# EBN_OLED_V01.net
KiCad netlist of a schematic drawn in EAGLE
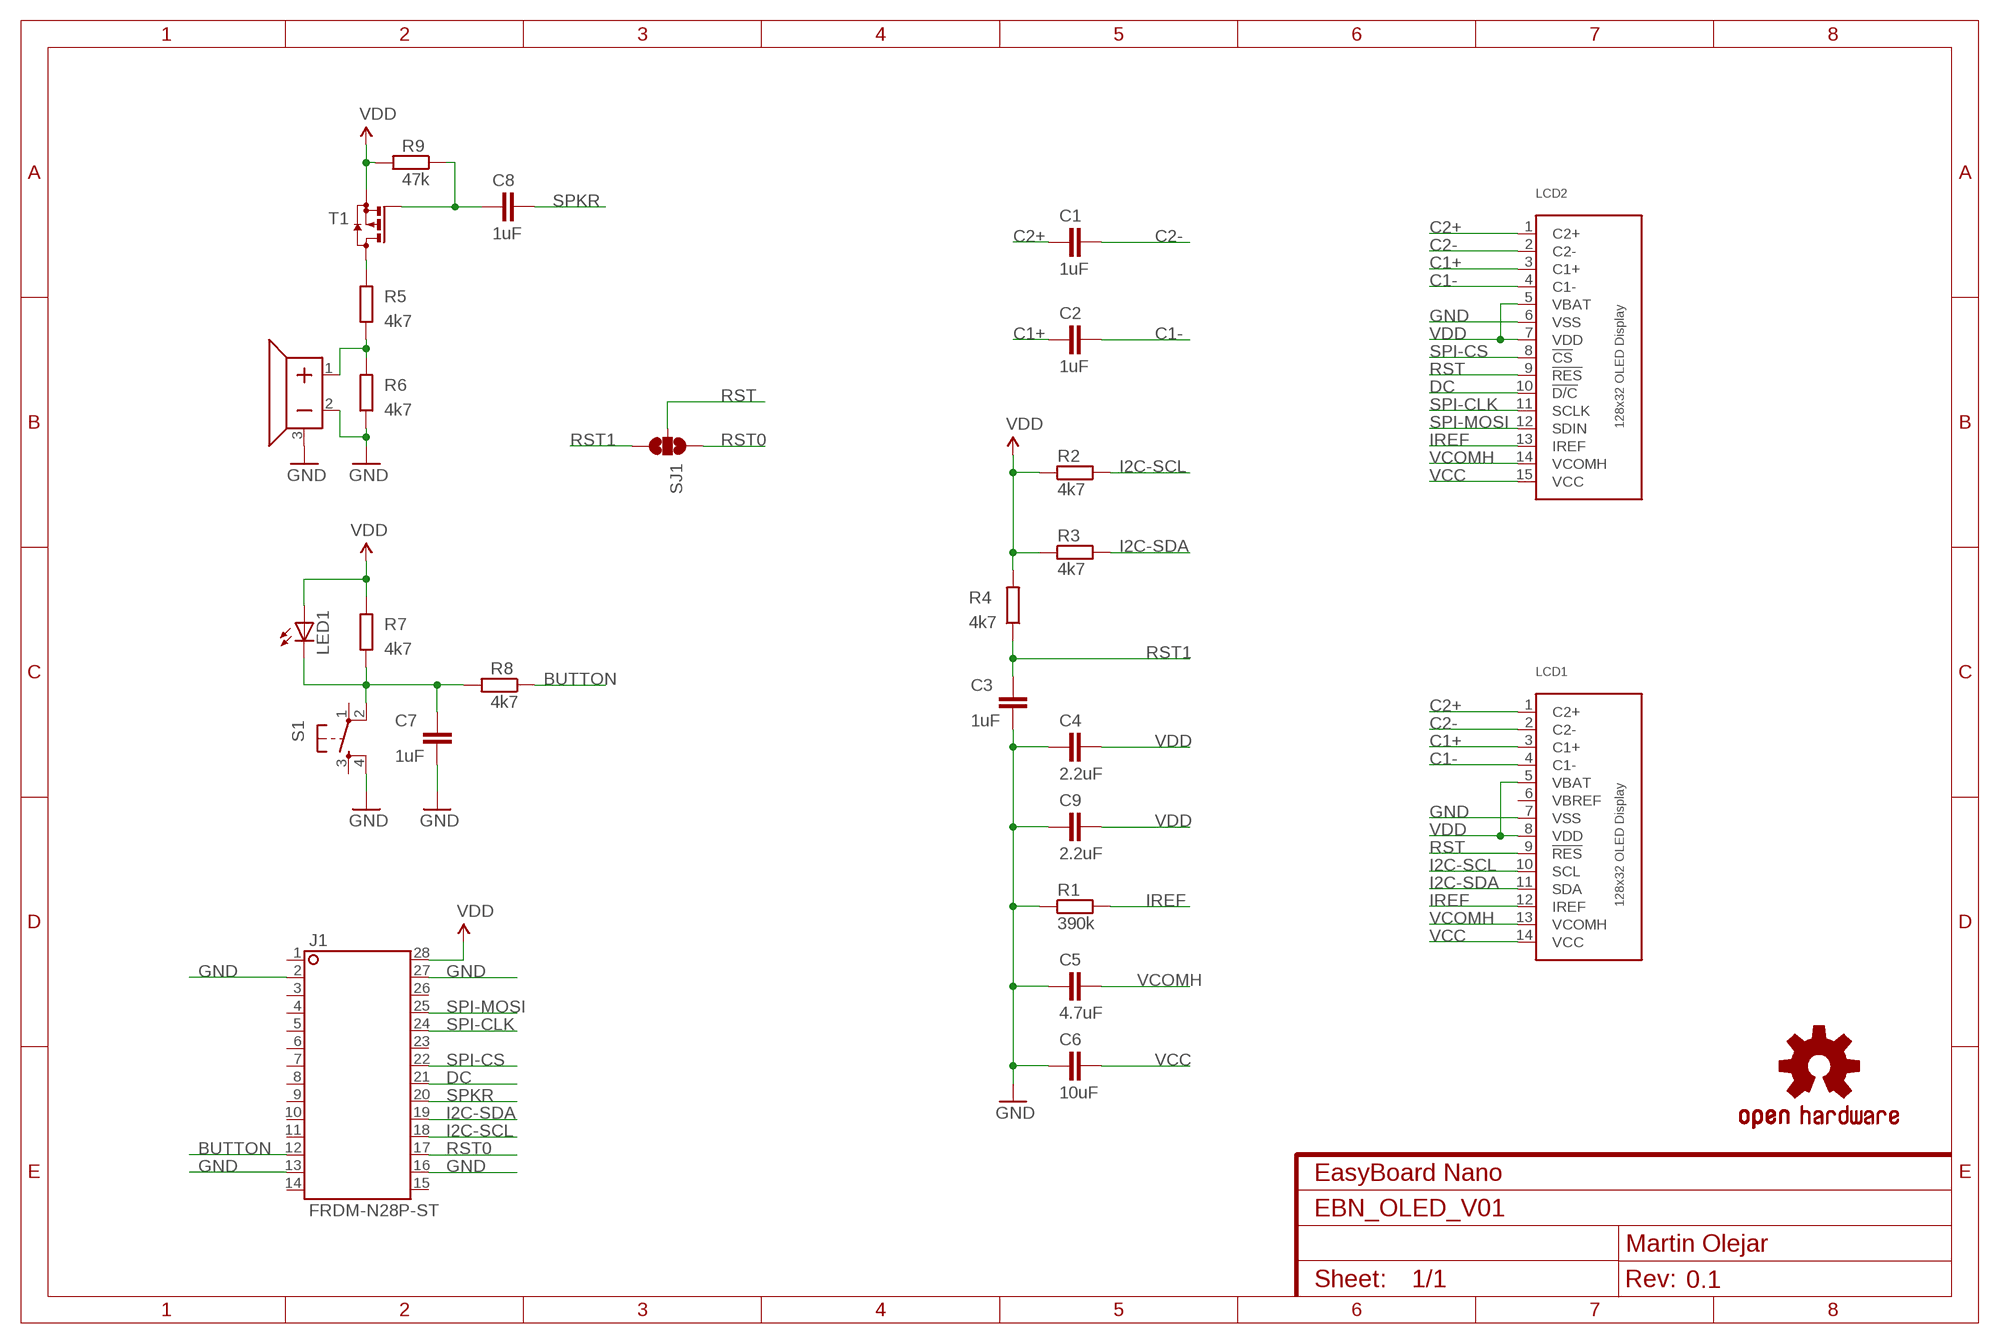
[diagram p0: schematic, sheet 1]

(export (version "E")
  (design (tool "Eeschema 10.0.6"))
  (components
    (comp (ref "C1")
      (value "1uF")
      (footprint "eagle-import:C0603")
      (libsource (lib "eagle-import") (part "C-EUC0603"))
    )
    (comp (ref "C2")
      (value "1uF")
      (footprint "eagle-import:C0603")
      (libsource (lib "eagle-import") (part "C-EUC0603"))
    )
    (comp (ref "C3")
      (value "1uF")
      (footprint "eagle-import:C0603")
      (libsource (lib "eagle-import") (part "C-EUC0603"))
    )
    (comp (ref "C4")
      (value "2.2uF")
      (footprint "eagle-import:C0603")
      (libsource (lib "eagle-import") (part "C-EUC0603"))
    )
    (comp (ref "C5")
      (value "4.7uF")
      (footprint "eagle-import:C0603")
      (libsource (lib "eagle-import") (part "C-EUC0603"))
    )
    (comp (ref "C6")
      (value "10uF")
      (footprint "eagle-import:C0603")
      (libsource (lib "eagle-import") (part "C-EUC0603"))
    )
    (comp (ref "C7")
      (value "1uF")
      (footprint "eagle-import:C0603")
      (libsource (lib "eagle-import") (part "C-EUC0603"))
    )
    (comp (ref "C8")
      (value "1uF")
      (footprint "eagle-import:C0603")
      (libsource (lib "eagle-import") (part "C-EUC0603"))
    )
    (comp (ref "C9")
      (value "2.2uF")
      (footprint "eagle-import:C0603")
      (libsource (lib "eagle-import") (part "C-EUC0603"))
    )
    (comp (ref "J1")
      (value "FRDM-N28P-ST")
      (footprint "eagle-import:FRDM-N28P-SHIELD")
      (libsource (lib "eagle-import") (part "FRDM-N28P-ST"))
    )
    (comp (ref "LCD1")
      (value "DISP_OLED_UG-2832HSWEG02")
      (footprint "eagle-import:UG-2832HSWEG02_WRAPUNDER")
      (libsource (lib "eagle-import") (part "DISP_OLED_UG-2832HSWEG02"))
    )
    (comp (ref "LCD2")
      (value "DISP_OLED_UG-2832HSWEG04WRAPAROUND")
      (footprint "eagle-import:UG-2832HSWEG04_WRAPAROUND")
      (libsource (lib "eagle-import") (part "DISP_OLED_UG-2832HSWEG04WRAPAROUND"))
    )
    (comp (ref "LED1")
      (value "LEDCHIPLED_0805")
      (footprint "eagle-import:CHIPLED_0805")
      (libsource (lib "eagle-import") (part "LEDCHIPLED_0805"))
    )
    (comp (ref "LOGO1")
      (value "OSHW-LOGOS")
      (footprint "eagle-import:OSHW-LOGO-S")
      (libsource (lib "eagle-import") (part "OSHW-LOGOS"))
    )
    (comp (ref "R1")
      (value "390k")
      (footprint "eagle-import:R0603")
      (libsource (lib "eagle-import") (part "R-EUR0603"))
    )
    (comp (ref "R2")
      (value "4k7")
      (footprint "eagle-import:R0603")
      (libsource (lib "eagle-import") (part "R-EUR0603"))
    )
    (comp (ref "R3")
      (value "4k7")
      (footprint "eagle-import:R0603")
      (libsource (lib "eagle-import") (part "R-EUR0603"))
    )
    (comp (ref "R4")
      (value "4k7")
      (footprint "eagle-import:R0603")
      (libsource (lib "eagle-import") (part "R-EUR0603"))
    )
    (comp (ref "R5")
      (value "4k7")
      (footprint "eagle-import:R0603")
      (libsource (lib "eagle-import") (part "R-EUR0603"))
    )
    (comp (ref "R6")
      (value "4k7")
      (footprint "eagle-import:R0603")
      (libsource (lib "eagle-import") (part "R-EUR0603"))
    )
    (comp (ref "R7")
      (value "4k7")
      (footprint "eagle-import:R0603")
      (libsource (lib "eagle-import") (part "R-EUR0603"))
    )
    (comp (ref "R8")
      (value "4k7")
      (footprint "eagle-import:R0603")
      (libsource (lib "eagle-import") (part "R-EUR0603"))
    )
    (comp (ref "R9")
      (value "47k")
      (footprint "eagle-import:R0603")
      (libsource (lib "eagle-import") (part "R-EUR0603"))
    )
    (comp (ref "S1")
      (value "SWITCH-TACT2")
      (footprint "eagle-import:EVQ-PLX")
      (libsource (lib "eagle-import") (part "SWITCH-TACT2"))
    )
    (comp (ref "SJ1")
      (value "SJ2W-S")
      (footprint "eagle-import:JUMPER-SMD-S2X")
      (libsource (lib "eagle-import") (part "SJ2W-S"))
    )
    (comp (ref "T1")
      (value "-PMOS-SOT23")
      (footprint "eagle-import:SOT23")
      (libsource (lib "eagle-import") (part "-PMOS-SOT23"))
    )
    (comp (ref "U$1")
      (value "SPEAKER")
      (footprint "eagle-import:BUZZER-5MM")
      (libsource (lib "eagle-import") (part "SPEAKER"))
    )
  )
  (nets
    (net (code "1") (name "/BUTTON") (class "Default")
      (node (ref "J1") (pin "12") (pinfunction "12_12") (pintype "passive"))
      (node (ref "R8") (pin "1") (pinfunction "1_1") (pintype "passive"))
    )
    (net (code "2") (name "/C1+") (class "Default")
      (node (ref "C2") (pin "1") (pinfunction "1_1") (pintype "passive"))
      (node (ref "LCD1") (pin "3") (pinfunction "C1+_3") (pintype "bidirectional"))
      (node (ref "LCD2") (pin "3") (pinfunction "C1+_3") (pintype "bidirectional"))
    )
    (net (code "3") (name "/C1-") (class "Default")
      (node (ref "C2") (pin "2") (pinfunction "2_2") (pintype "passive"))
      (node (ref "LCD1") (pin "4") (pinfunction "C1-_4") (pintype "bidirectional"))
      (node (ref "LCD2") (pin "4") (pinfunction "C1-_4") (pintype "bidirectional"))
    )
    (net (code "4") (name "/C2+") (class "Default")
      (node (ref "C1") (pin "1") (pinfunction "1_1") (pintype "passive"))
      (node (ref "LCD1") (pin "1") (pinfunction "C2+_1") (pintype "bidirectional"))
      (node (ref "LCD2") (pin "1") (pinfunction "C2+_1") (pintype "bidirectional"))
    )
    (net (code "5") (name "/C2-") (class "Default")
      (node (ref "C1") (pin "2") (pinfunction "2_2") (pintype "passive"))
      (node (ref "LCD1") (pin "2") (pinfunction "C2-_2") (pintype "bidirectional"))
      (node (ref "LCD2") (pin "2") (pinfunction "C2-_2") (pintype "bidirectional"))
    )
    (net (code "6") (name "/DC") (class "Default")
      (node (ref "J1") (pin "21") (pinfunction "21_21") (pintype "passive"))
      (node (ref "LCD2") (pin "10") (pinfunction "~{D/C}_10") (pintype "bidirectional"))
    )
    (net (code "7") (name "/I2C-SCL") (class "Default")
      (node (ref "J1") (pin "18") (pinfunction "18_18") (pintype "passive"))
      (node (ref "LCD1") (pin "10") (pinfunction "SCL_10") (pintype "bidirectional"))
      (node (ref "R2") (pin "2") (pinfunction "2_2") (pintype "passive"))
    )
    (net (code "8") (name "/I2C-SDA") (class "Default")
      (node (ref "J1") (pin "19") (pinfunction "19_19") (pintype "passive"))
      (node (ref "LCD1") (pin "11") (pinfunction "SDA_11") (pintype "bidirectional"))
      (node (ref "R3") (pin "2") (pinfunction "2_2") (pintype "passive"))
    )
    (net (code "9") (name "/IREF") (class "Default")
      (node (ref "LCD1") (pin "12") (pinfunction "IREF_12") (pintype "bidirectional"))
      (node (ref "LCD2") (pin "13") (pinfunction "IREF_13") (pintype "bidirectional"))
      (node (ref "R1") (pin "2") (pinfunction "2_2") (pintype "passive"))
    )
    (net (code "10") (name "/RST") (class "Default")
      (node (ref "LCD1") (pin "9") (pinfunction "~{RES}_9") (pintype "bidirectional"))
      (node (ref "LCD2") (pin "9") (pinfunction "~{RES}_9") (pintype "bidirectional"))
      (node (ref "SJ1") (pin "2") (pinfunction "2_2") (pintype "passive"))
    )
    (net (code "11") (name "/RST0") (class "Default")
      (node (ref "J1") (pin "17") (pinfunction "17_17") (pintype "passive"))
      (node (ref "SJ1") (pin "1") (pinfunction "1_1") (pintype "passive"))
    )
    (net (code "12") (name "/RST1") (class "Default")
      (node (ref "C3") (pin "2") (pinfunction "2_2") (pintype "passive"))
      (node (ref "R4") (pin "1") (pinfunction "1_1") (pintype "passive"))
      (node (ref "SJ1") (pin "3") (pinfunction "3_3") (pintype "passive"))
    )
    (net (code "13") (name "/SPI-CLK") (class "Default")
      (node (ref "J1") (pin "24") (pinfunction "24_24") (pintype "passive"))
      (node (ref "LCD2") (pin "11") (pinfunction "SCLK_11") (pintype "bidirectional"))
    )
    (net (code "14") (name "/SPI-CS") (class "Default")
      (node (ref "J1") (pin "22") (pinfunction "22_22") (pintype "passive"))
      (node (ref "LCD2") (pin "8") (pinfunction "~{CS}_8") (pintype "bidirectional"))
    )
    (net (code "15") (name "/SPI-MOSI") (class "Default")
      (node (ref "J1") (pin "25") (pinfunction "25_25") (pintype "passive"))
      (node (ref "LCD2") (pin "12") (pinfunction "SDIN_12") (pintype "bidirectional"))
    )
    (net (code "16") (name "/SPKR") (class "Default")
      (node (ref "C8") (pin "2") (pinfunction "2_2") (pintype "passive"))
      (node (ref "J1") (pin "20") (pinfunction "20_20") (pintype "passive"))
    )
    (net (code "17") (name "/VBREF") (class "Default")
      (node (ref "LCD1") (pin "6") (pinfunction "VBREF_6") (pintype "power_in"))
    )
    (net (code "18") (name "/VCC") (class "Default")
      (node (ref "C6") (pin "2") (pinfunction "2_2") (pintype "passive"))
      (node (ref "LCD1") (pin "14") (pinfunction "VCC_14") (pintype "power_in"))
      (node (ref "LCD2") (pin "15") (pinfunction "VCC_15") (pintype "bidirectional"))
    )
    (net (code "19") (name "/VCOMH") (class "Default")
      (node (ref "C5") (pin "2") (pinfunction "2_2") (pintype "passive"))
      (node (ref "LCD1") (pin "13") (pinfunction "VCOMH_13") (pintype "power_in"))
      (node (ref "LCD2") (pin "14") (pinfunction "VCOMH_14") (pintype "bidirectional"))
    )
    (net (code "20") (name "GND") (class "Default")
      (node (ref "C3") (pin "1") (pinfunction "1_1") (pintype "passive"))
      (node (ref "C4") (pin "1") (pinfunction "1_1") (pintype "passive"))
      (node (ref "C5") (pin "1") (pinfunction "1_1") (pintype "passive"))
      (node (ref "C6") (pin "1") (pinfunction "1_1") (pintype "passive"))
      (node (ref "C7") (pin "1") (pinfunction "1_1") (pintype "passive"))
      (node (ref "C9") (pin "1") (pinfunction "1_1") (pintype "passive"))
      (node (ref "J1") (pin "13") (pinfunction "13_13") (pintype "passive"))
      (node (ref "J1") (pin "16") (pinfunction "16_16") (pintype "passive"))
      (node (ref "J1") (pin "2") (pinfunction "2_2") (pintype "passive"))
      (node (ref "J1") (pin "27") (pinfunction "27_27") (pintype "passive"))
      (node (ref "LCD1") (pin "7") (pinfunction "VSS_7") (pintype "power_in"))
      (node (ref "LCD2") (pin "6") (pinfunction "VSS_6") (pintype "bidirectional"))
      (node (ref "R1") (pin "1") (pinfunction "1_1") (pintype "passive"))
      (node (ref "R6") (pin "1") (pinfunction "1_1") (pintype "passive"))
      (node (ref "S1") (pin "4") (pinfunction "4_4") (pintype "passive"))
      (node (ref "U$1") (pin "2") (pinfunction "2_2") (pintype "bidirectional"))
      (node (ref "U$1") (pin "3") (pinfunction "3_3") (pintype "bidirectional"))
    )
    (net (code "21") (name "Net-(C7-Pad2)") (class "Default")
      (node (ref "C7") (pin "2") (pinfunction "2_2") (pintype "passive"))
      (node (ref "LED1") (pin "C") (pinfunction "C_C") (pintype "passive"))
      (node (ref "R7") (pin "1") (pinfunction "1_1") (pintype "passive"))
      (node (ref "R8") (pin "2") (pinfunction "2_2") (pintype "passive"))
      (node (ref "S1") (pin "2") (pinfunction "2_2") (pintype "passive"))
    )
    (net (code "22") (name "Net-(R5-Pad1)") (class "Default")
      (node (ref "R5") (pin "1") (pinfunction "1_1") (pintype "passive"))
      (node (ref "R6") (pin "2") (pinfunction "2_2") (pintype "passive"))
      (node (ref "U$1") (pin "1") (pinfunction "1_1") (pintype "bidirectional"))
    )
    (net (code "23") (name "Net-(T1-D)") (class "Default")
      (node (ref "R5") (pin "2") (pinfunction "2_2") (pintype "passive"))
      (node (ref "T1") (pin "3") (pinfunction "D_3") (pintype "passive"))
    )
    (net (code "24") (name "Net-(T1-G)") (class "Default")
      (node (ref "C8") (pin "1") (pinfunction "1_1") (pintype "passive"))
      (node (ref "R9") (pin "1") (pinfunction "1_1") (pintype "passive"))
      (node (ref "T1") (pin "1") (pinfunction "G_1") (pintype "passive"))
    )
    (net (code "25") (name "VDD") (class "Default")
      (node (ref "C4") (pin "2") (pinfunction "2_2") (pintype "passive"))
      (node (ref "C9") (pin "2") (pinfunction "2_2") (pintype "passive"))
      (node (ref "J1") (pin "28") (pinfunction "28_28") (pintype "passive"))
      (node (ref "LCD1") (pin "5") (pinfunction "VBAT_5") (pintype "power_in"))
      (node (ref "LCD1") (pin "8") (pinfunction "VDD_8") (pintype "power_in"))
      (node (ref "LCD2") (pin "5") (pinfunction "VBAT_5") (pintype "bidirectional"))
      (node (ref "LCD2") (pin "7") (pinfunction "VDD_7") (pintype "bidirectional"))
      (node (ref "LED1") (pin "A") (pinfunction "A_A") (pintype "passive"))
      (node (ref "R2") (pin "1") (pinfunction "1_1") (pintype "passive"))
      (node (ref "R3") (pin "1") (pinfunction "1_1") (pintype "passive"))
      (node (ref "R4") (pin "2") (pinfunction "2_2") (pintype "passive"))
      (node (ref "R7") (pin "2") (pinfunction "2_2") (pintype "passive"))
      (node (ref "R9") (pin "2") (pinfunction "2_2") (pintype "passive"))
      (node (ref "T1") (pin "2") (pinfunction "S_2") (pintype "passive"))
    )
    (net (code "26") (name "unconnected-(J1-Pad1)") (class "Default")
      (node (ref "J1") (pin "1") (pinfunction "1_1") (pintype "passive"))
    )
    (net (code "27") (name "unconnected-(J1-Pad3)") (class "Default")
      (node (ref "J1") (pin "3") (pinfunction "3_3") (pintype "passive"))
    )
    (net (code "28") (name "unconnected-(J1-Pad4)") (class "Default")
      (node (ref "J1") (pin "4") (pinfunction "4_4") (pintype "passive"))
    )
    (net (code "29") (name "unconnected-(J1-Pad5)") (class "Default")
      (node (ref "J1") (pin "5") (pinfunction "5_5") (pintype "passive"))
    )
    (net (code "30") (name "unconnected-(J1-Pad6)") (class "Default")
      (node (ref "J1") (pin "6") (pinfunction "6_6") (pintype "passive"))
    )
    (net (code "31") (name "unconnected-(J1-Pad7)") (class "Default")
      (node (ref "J1") (pin "7") (pinfunction "7_7") (pintype "passive"))
    )
    (net (code "32") (name "unconnected-(J1-Pad8)") (class "Default")
      (node (ref "J1") (pin "8") (pinfunction "8_8") (pintype "passive"))
    )
    (net (code "33") (name "unconnected-(J1-Pad9)") (class "Default")
      (node (ref "J1") (pin "9") (pinfunction "9_9") (pintype "passive"))
    )
    (net (code "34") (name "unconnected-(J1-Pad10)") (class "Default")
      (node (ref "J1") (pin "10") (pinfunction "10_10") (pintype "passive"))
    )
    (net (code "35") (name "unconnected-(J1-Pad11)") (class "Default")
      (node (ref "J1") (pin "11") (pinfunction "11_11") (pintype "passive"))
    )
    (net (code "36") (name "unconnected-(J1-Pad14)") (class "Default")
      (node (ref "J1") (pin "14") (pinfunction "14_14") (pintype "passive"))
    )
    (net (code "37") (name "unconnected-(J1-Pad15)") (class "Default")
      (node (ref "J1") (pin "15") (pinfunction "15_15") (pintype "passive"))
    )
    (net (code "38") (name "unconnected-(J1-Pad23)") (class "Default")
      (node (ref "J1") (pin "23") (pinfunction "23_23") (pintype "passive"))
    )
    (net (code "39") (name "unconnected-(J1-Pad26)") (class "Default")
      (node (ref "J1") (pin "26") (pinfunction "26_26") (pintype "passive"))
    )
    (net (code "40") (name "unconnected-(S1-Pad1)") (class "Default")
      (node (ref "S1") (pin "1") (pinfunction "1_1") (pintype "passive"))
    )
    (net (code "41") (name "unconnected-(S1-Pad3)") (class "Default")
      (node (ref "S1") (pin "3") (pinfunction "3_3") (pintype "passive"))
    )
  )
)
